# I2C-7-Segment-Backpack-dot36inch.net
KiCad netlist of a schematic drawn in EAGLE
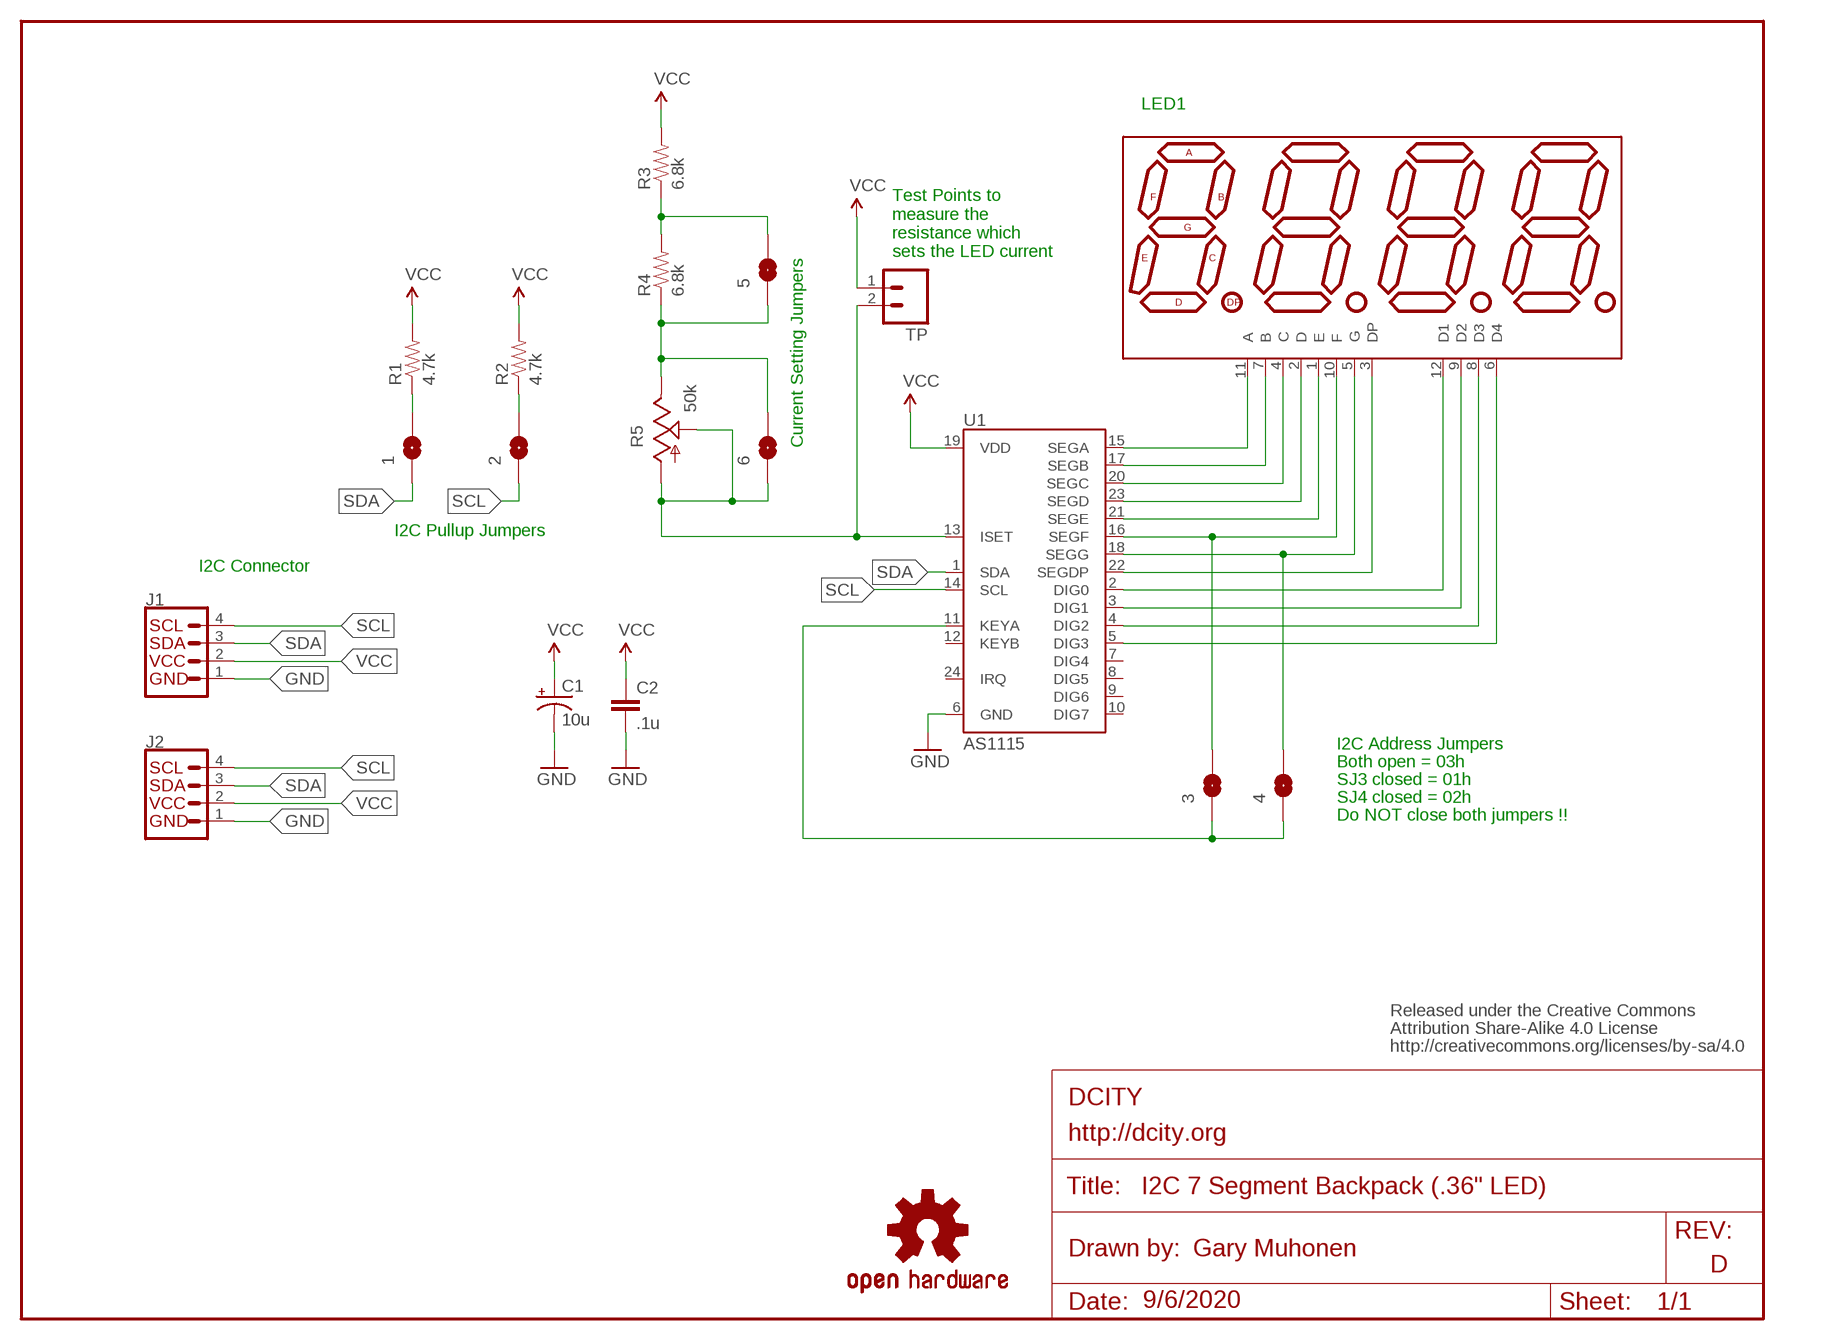
[diagram p0: schematic, sheet 1]

(export (version "E")
  (design (tool "Eeschema 10.0.6"))
  (components
    (comp (ref "1")
      (value "SOLDERJUMPERNO")
      (footprint "eagle-import:SJ_2S-NO")
      (libsource (lib "eagle-import") (part "SOLDERJUMPERNO"))
    )
    (comp (ref "2")
      (value "SOLDERJUMPERNO")
      (footprint "eagle-import:SJ_2S-NO")
      (libsource (lib "eagle-import") (part "SOLDERJUMPERNO"))
    )
    (comp (ref "3")
      (value "SOLDERJUMPERNO")
      (footprint "eagle-import:SJ_2S-NO")
      (libsource (lib "eagle-import") (part "SOLDERJUMPERNO"))
    )
    (comp (ref "4")
      (value "SOLDERJUMPERNO")
      (footprint "eagle-import:SJ_2S-NO")
      (libsource (lib "eagle-import") (part "SOLDERJUMPERNO"))
    )
    (comp (ref "5")
      (value "SOLDERJUMPERNO")
      (footprint "eagle-import:SJ_2S-NO")
      (libsource (lib "eagle-import") (part "SOLDERJUMPERNO"))
    )
    (comp (ref "6")
      (value "SOLDERJUMPERNO")
      (footprint "eagle-import:SJ_2S-NO")
      (libsource (lib "eagle-import") (part "SOLDERJUMPERNO"))
    )
    (comp (ref "C1")
      (value "10u")
      (footprint "eagle-import:0805-POL")
      (libsource (lib "eagle-import") (part "CAP_POL0805"))
    )
    (comp (ref "C2")
      (value ".1u")
      (footprint "eagle-import:0805-CAP")
      (libsource (lib "eagle-import") (part "CAP0805"))
    )
    (comp (ref "DISP1")
      (value "LED1")
      (footprint "eagle-import:7-SEGMENT-4DIGIT-PT4")
      (libsource (lib "eagle-import") (part "7-SEGMENT-4DIGIT-COUNTER-PT4"))
    )
    (comp (ref "J1")
      (value "QWIIC_RIGHT_ANGLE")
      (footprint "eagle-import:JST04_1MM_RA")
      (libsource (lib "eagle-import") (part "QWIIC_CONNECTORJS-1MM"))
    )
    (comp (ref "J2")
      (value "QWIIC_RIGHT_ANGLE")
      (footprint "eagle-import:JST04_1MM_RA")
      (libsource (lib "eagle-import") (part "QWIIC_CONNECTORJS-1MM"))
    )
    (comp (ref "LOGO1")
      (value "OSHW-LOGOS")
      (footprint "eagle-import:OSHW-LOGO-S")
      (libsource (lib "eagle-import") (part "OSHW-LOGOS"))
    )
    (comp (ref "R1")
      (value "4.7k")
      (footprint "eagle-import:0805-RES")
      (libsource (lib "eagle-import") (part "RESISTOR0805"))
    )
    (comp (ref "R2")
      (value "4.7k")
      (footprint "eagle-import:0805-RES")
      (libsource (lib "eagle-import") (part "RESISTOR0805"))
    )
    (comp (ref "R3")
      (value "6.8k")
      (footprint "eagle-import:0805-RES")
      (libsource (lib "eagle-import") (part "RESISTOR0805"))
    )
    (comp (ref "R4")
      (value "6.8k")
      (footprint "eagle-import:0805-RES")
      (libsource (lib "eagle-import") (part "RESISTOR0805"))
    )
    (comp (ref "R5")
      (value "50k")
      (footprint "eagle-import:POT-TC33X")
      (libsource (lib "eagle-import") (part "POT-TC33X"))
    )
    (comp (ref "TP")
      (value "M02PTH")
      (footprint "eagle-import:1X02")
      (libsource (lib "eagle-import") (part "M02PTH"))
    )
    (comp (ref "U$4")
      (value "CREATIVE_COMMONS")
      (footprint "eagle-import:CREATIVE_COMMONS")
      (libsource (lib "eagle-import") (part "CREATIVE_COMMONS"))
    )
    (comp (ref "U1")
      (value "AS1115")
      (footprint "eagle-import:TSSOP24-NO-HS")
      (libsource (lib "eagle-import") (part "AS1115-NO-HS"))
    )
  )
  (nets
    (net (code "1") (name "GND") (class "Default")
      (node (ref "C1") (pin "-") (pinfunction "-_-") (pintype "passive"))
      (node (ref "C2") (pin "2") (pinfunction "2_2") (pintype "passive"))
      (node (ref "J1") (pin "1") (pinfunction "1_1") (pintype "power_in"))
      (node (ref "J2") (pin "1") (pinfunction "1_1") (pintype "power_in"))
      (node (ref "U1") (pin "6") (pinfunction "GND_6") (pintype "bidirectional"))
    )
    (net (code "2") (name "Net-(1-Pad2)") (class "Default")
      (node (ref "1") (pin "2") (pinfunction "2_2") (pintype "passive"))
      (node (ref "R1") (pin "1") (pinfunction "1_1") (pintype "passive"))
    )
    (net (code "3") (name "Net-(2-Pad2)") (class "Default")
      (node (ref "2") (pin "2") (pinfunction "2_2") (pintype "passive"))
      (node (ref "R2") (pin "1") (pinfunction "1_1") (pintype "passive"))
    )
    (net (code "4") (name "Net-(5-Pad2)") (class "Default")
      (node (ref "5") (pin "2") (pinfunction "2_2") (pintype "passive"))
      (node (ref "R3") (pin "1") (pinfunction "1_1") (pintype "passive"))
      (node (ref "R4") (pin "2") (pinfunction "2_2") (pintype "passive"))
    )
    (net (code "5") (name "Net-(DISP1-A)") (class "Default")
      (node (ref "DISP1") (pin "11") (pinfunction "A_11") (pintype "bidirectional"))
      (node (ref "U1") (pin "15") (pinfunction "SEGA_15") (pintype "bidirectional"))
    )
    (net (code "6") (name "Net-(DISP1-B)") (class "Default")
      (node (ref "DISP1") (pin "7") (pinfunction "B_7") (pintype "bidirectional"))
      (node (ref "U1") (pin "17") (pinfunction "SEGB_17") (pintype "bidirectional"))
    )
    (net (code "7") (name "Net-(DISP1-C)") (class "Default")
      (node (ref "DISP1") (pin "4") (pinfunction "C_4") (pintype "bidirectional"))
      (node (ref "U1") (pin "20") (pinfunction "SEGC_20") (pintype "bidirectional"))
    )
    (net (code "8") (name "Net-(DISP1-D)") (class "Default")
      (node (ref "DISP1") (pin "2") (pinfunction "D_2") (pintype "bidirectional"))
      (node (ref "U1") (pin "23") (pinfunction "SEGD_23") (pintype "bidirectional"))
    )
    (net (code "9") (name "Net-(DISP1-D1)") (class "Default")
      (node (ref "DISP1") (pin "12") (pinfunction "D1_12") (pintype "bidirectional"))
      (node (ref "U1") (pin "2") (pinfunction "DIG0_2") (pintype "bidirectional"))
    )
    (net (code "10") (name "Net-(DISP1-D2)") (class "Default")
      (node (ref "DISP1") (pin "9") (pinfunction "D2_9") (pintype "bidirectional"))
      (node (ref "U1") (pin "3") (pinfunction "DIG1_3") (pintype "bidirectional"))
    )
    (net (code "11") (name "Net-(DISP1-D3)") (class "Default")
      (node (ref "DISP1") (pin "8") (pinfunction "D3_8") (pintype "bidirectional"))
      (node (ref "U1") (pin "4") (pinfunction "DIG2_4") (pintype "bidirectional"))
    )
    (net (code "12") (name "Net-(DISP1-D4)") (class "Default")
      (node (ref "DISP1") (pin "6") (pinfunction "D4_6") (pintype "bidirectional"))
      (node (ref "U1") (pin "5") (pinfunction "DIG3_5") (pintype "bidirectional"))
    )
    (net (code "13") (name "Net-(DISP1-DP)") (class "Default")
      (node (ref "DISP1") (pin "3") (pinfunction "DP_3") (pintype "bidirectional"))
      (node (ref "U1") (pin "22") (pinfunction "SEGDP_22") (pintype "bidirectional"))
    )
    (net (code "14") (name "Net-(DISP1-E)") (class "Default")
      (node (ref "DISP1") (pin "1") (pinfunction "E_1") (pintype "bidirectional"))
      (node (ref "U1") (pin "21") (pinfunction "SEGE_21") (pintype "bidirectional"))
    )
    (net (code "15") (name "Net-(DISP1-F)") (class "Default")
      (node (ref "3") (pin "2") (pinfunction "2_2") (pintype "passive"))
      (node (ref "DISP1") (pin "10") (pinfunction "F_10") (pintype "bidirectional"))
      (node (ref "U1") (pin "16") (pinfunction "SEGF_16") (pintype "bidirectional"))
    )
    (net (code "16") (name "Net-(DISP1-G)") (class "Default")
      (node (ref "4") (pin "2") (pinfunction "2_2") (pintype "passive"))
      (node (ref "DISP1") (pin "5") (pinfunction "G_5") (pintype "bidirectional"))
      (node (ref "U1") (pin "18") (pinfunction "SEGG_18") (pintype "bidirectional"))
    )
    (net (code "17") (name "Net-(R5-A)") (class "Default")
      (node (ref "6") (pin "1") (pinfunction "1_1") (pintype "passive"))
      (node (ref "R5") (pin "1") (pinfunction "A_1") (pintype "passive"))
      (node (ref "R5") (pin "2") (pinfunction "S_2") (pintype "passive"))
      (node (ref "TP") (pin "2") (pinfunction "2_2") (pintype "passive"))
      (node (ref "U1") (pin "13") (pinfunction "ISET_13") (pintype "bidirectional"))
    )
    (net (code "18") (name "Net-(R5-E)") (class "Default")
      (node (ref "5") (pin "1") (pinfunction "1_1") (pintype "passive"))
      (node (ref "6") (pin "2") (pinfunction "2_2") (pintype "passive"))
      (node (ref "R4") (pin "1") (pinfunction "1_1") (pintype "passive"))
      (node (ref "R5") (pin "3") (pinfunction "E_3") (pintype "passive"))
    )
    (net (code "19") (name "Net-(U1-KEYA)") (class "Default")
      (node (ref "3") (pin "1") (pinfunction "1_1") (pintype "passive"))
      (node (ref "4") (pin "1") (pinfunction "1_1") (pintype "passive"))
      (node (ref "U1") (pin "11") (pinfunction "KEYA_11") (pintype "bidirectional"))
    )
    (net (code "20") (name "SCL") (class "Default")
      (node (ref "2") (pin "1") (pinfunction "1_1") (pintype "passive"))
      (node (ref "J1") (pin "4") (pinfunction "4_4") (pintype "passive"))
      (node (ref "J2") (pin "4") (pinfunction "4_4") (pintype "passive"))
      (node (ref "U1") (pin "14") (pinfunction "SCL_14") (pintype "bidirectional"))
    )
    (net (code "21") (name "SDA") (class "Default")
      (node (ref "1") (pin "1") (pinfunction "1_1") (pintype "passive"))
      (node (ref "J1") (pin "3") (pinfunction "3_3") (pintype "passive"))
      (node (ref "J2") (pin "3") (pinfunction "3_3") (pintype "passive"))
      (node (ref "U1") (pin "1") (pinfunction "SDA_1") (pintype "bidirectional"))
    )
    (net (code "22") (name "VCC") (class "Default")
      (node (ref "C1") (pin "+") (pinfunction "+_+") (pintype "passive"))
      (node (ref "C2") (pin "1") (pinfunction "1_1") (pintype "passive"))
      (node (ref "J1") (pin "2") (pinfunction "2_2") (pintype "power_in"))
      (node (ref "J2") (pin "2") (pinfunction "2_2") (pintype "power_in"))
      (node (ref "R1") (pin "2") (pinfunction "2_2") (pintype "passive"))
      (node (ref "R2") (pin "2") (pinfunction "2_2") (pintype "passive"))
      (node (ref "R3") (pin "2") (pinfunction "2_2") (pintype "passive"))
      (node (ref "TP") (pin "1") (pinfunction "1_1") (pintype "passive"))
      (node (ref "U1") (pin "19") (pinfunction "VDD_19") (pintype "bidirectional"))
    )
    (net (code "23") (name "unconnected-(U1-DIG4-Pad7)") (class "Default")
      (node (ref "U1") (pin "7") (pinfunction "DIG4_7") (pintype "bidirectional"))
    )
    (net (code "24") (name "unconnected-(U1-DIG5-Pad8)") (class "Default")
      (node (ref "U1") (pin "8") (pinfunction "DIG5_8") (pintype "bidirectional"))
    )
    (net (code "25") (name "unconnected-(U1-DIG6-Pad9)") (class "Default")
      (node (ref "U1") (pin "9") (pinfunction "DIG6_9") (pintype "bidirectional"))
    )
    (net (code "26") (name "unconnected-(U1-DIG7-Pad10)") (class "Default")
      (node (ref "U1") (pin "10") (pinfunction "DIG7_10") (pintype "bidirectional"))
    )
    (net (code "27") (name "unconnected-(U1-IRQ-Pad24)") (class "Default")
      (node (ref "U1") (pin "24") (pinfunction "IRQ_24") (pintype "bidirectional"))
    )
    (net (code "28") (name "unconnected-(U1-KEYB-Pad12)") (class "Default")
      (node (ref "U1") (pin "12") (pinfunction "KEYB_12") (pintype "bidirectional"))
    )
  )
)
